# Motor_Control.net
KiCad netlist of a schematic drawn in Altium Designer
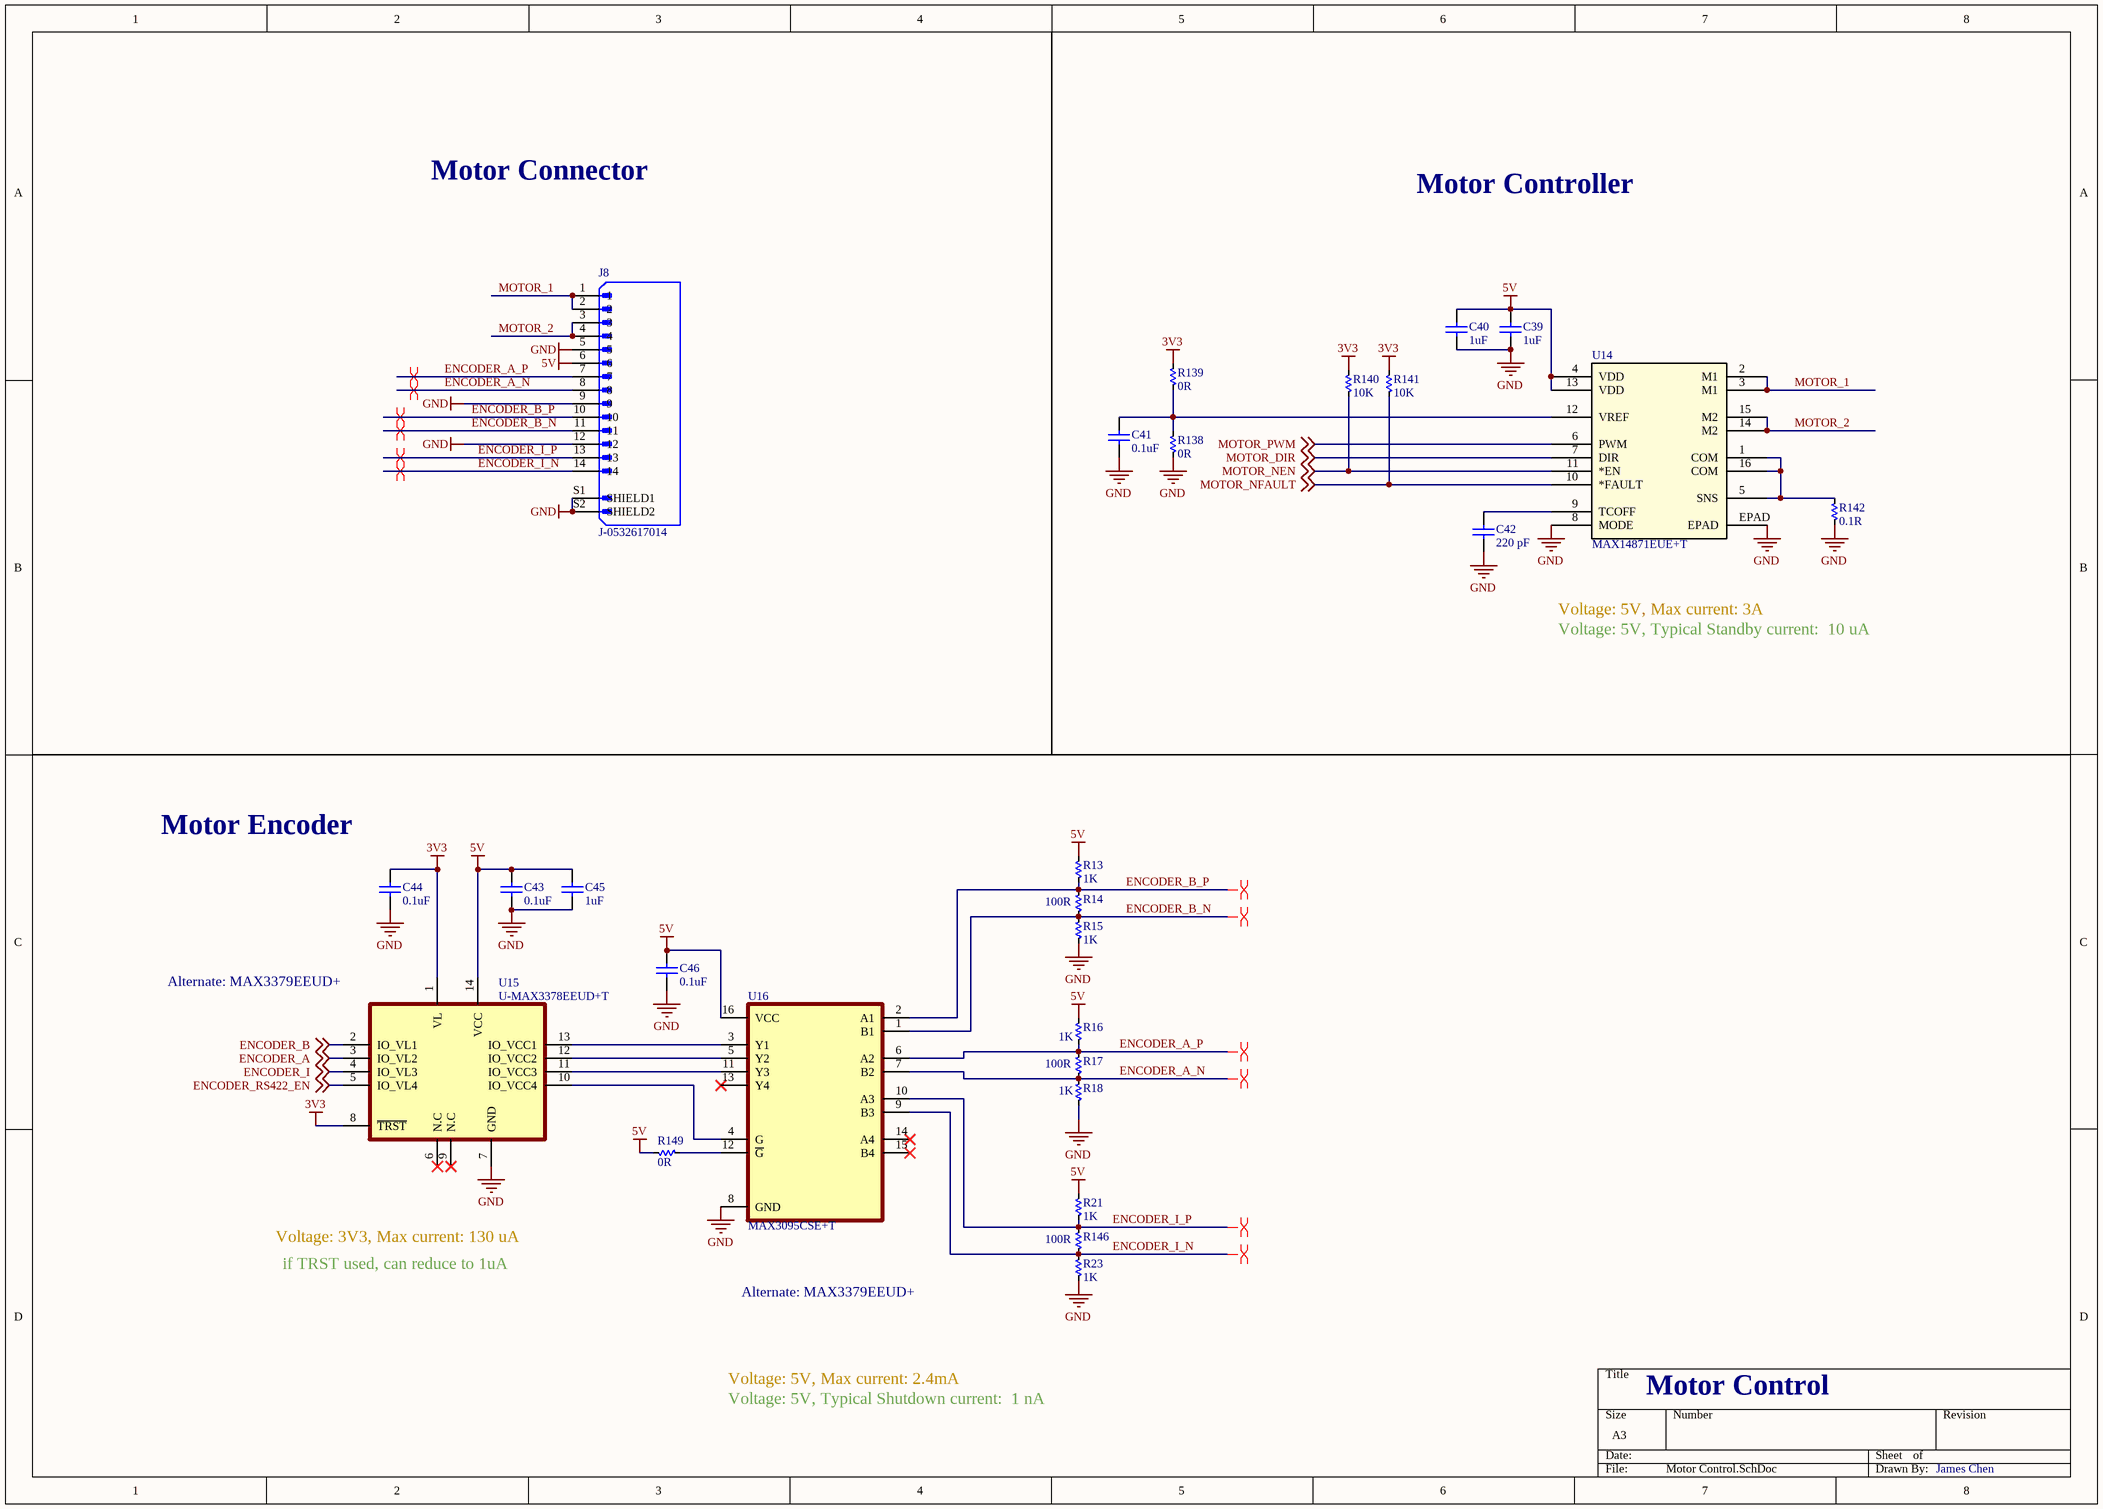
[diagram p0: Motor Control.SchDoc]

(export (version "E")
  (design (tool "Eeschema 10.0.6"))
  (components
    (comp (ref "C39")
      (value "1uF")
      (footprint "0603")
      (description "CAP CER 1UF 25V X7R 0603")
      (fields (field (name "DISTRIBUTOR PART #") "311-1802-1-ND") (field (name "MANUFACTURER") "Yageo"))
      (libsource (lib "OBC Development Board") (part "CC-105-K-25V-X7R-0603"))
    )
    (comp (ref "C40")
      (value "1uF")
      (footprint "0603")
      (description "CAP CER 1UF 25V X7R 0603")
      (fields (field (name "DISTRIBUTOR PART #") "311-1802-1-ND") (field (name "MANUFACTURER") "Yageo"))
      (libsource (lib "OBC Development Board") (part "CC-105-K-25V-X7R-0603"))
    )
    (comp (ref "C41")
      (value "0.1uF")
      (footprint "0603")
      (description "0.1 µF ±10% 25V Ceramic Capacitor X7R 0603 (1608 Metric)")
      (fields
        (field (name "DISTRIBUTOR PART #") "1276-1006-1-ND")
        (field (name "MANUFACTURER") "Samsung Electro-Mechanics")
      )
      (libsource (lib "OBC Development Board") (part "CC-104-K-25V-X7R-0603"))
    )
    (comp (ref "C42")
      (value "220 pF")
      (footprint "0603")
      (description "15 pF ±1% 50V Ceramic Capacitor C0G, NP0 0201 (0603 Metric)")
      (fields
        (field (name "DISTRIBUTOR PART #") "1276-1048-1-ND")
        (field (name "MANUFACTURER") "Samsung Electro-Mechanics")
      )
      (libsource (lib "OBC Development Board") (part "CC-228-J-50V-C0G-0603"))
    )
    (comp (ref "C43")
      (value "0.1uF")
      (footprint "0603")
      (description "0.1 µF ±10% 25V Ceramic Capacitor X7R 0603 (1608 Metric)")
      (fields
        (field (name "DISTRIBUTOR PART #") "1276-1006-1-ND")
        (field (name "MANUFACTURER") "Samsung Electro-Mechanics")
      )
      (libsource (lib "OBC Development Board") (part "CC-104-K-25V-X7R-0603"))
    )
    (comp (ref "C44")
      (value "0.1uF")
      (footprint "0603")
      (description "0.1 µF ±10% 25V Ceramic Capacitor X7R 0603 (1608 Metric)")
      (fields
        (field (name "DISTRIBUTOR PART #") "1276-1006-1-ND")
        (field (name "MANUFACTURER") "Samsung Electro-Mechanics")
      )
      (libsource (lib "OBC Development Board") (part "CC-104-K-25V-X7R-0603"))
    )
    (comp (ref "C45")
      (value "1uF")
      (footprint "0603")
      (description "CAP CER 1UF 25V X7R 0603")
      (fields (field (name "DISTRIBUTOR PART #") "311-1802-1-ND") (field (name "MANUFACTURER") "Yageo"))
      (libsource (lib "OBC Development Board") (part "CC-105-K-25V-X7R-0603"))
    )
    (comp (ref "C46")
      (value "0.1uF")
      (footprint "0603")
      (description "0.1 µF ±10% 25V Ceramic Capacitor X7R 0603 (1608 Metric)")
      (fields
        (field (name "DISTRIBUTOR PART #") "1276-1006-1-ND")
        (field (name "MANUFACTURER") "Samsung Electro-Mechanics")
      )
      (libsource (lib "OBC Development Board") (part "CC-104-K-25V-X7R-0603"))
    )
    (comp (ref "J8")
      (value "J-0532617014")
      (footprint "J-532617014")
      (description "Connector Header Surface Mount, Right Angle 14 position 0.049 (1.25mm)")
      (fields (field (name "MANUFACTURER") "Molex") (field (name "MANUFACTURER PART #") "0532617014"))
      (libsource (lib "OBC Development Board") (part "J-0532617014"))
    )
    (comp (ref "R13")
      (value "1K")
      (footprint "0603")
      (description "RES SMD 1K OHM 1% 1/16W 0603")
      (fields
        (field (name "DISTRIBUTOR PART #") "A102226CT-ND")
        (field (name "MANUFACTURER") "TE Connectivity Passive Product")
      )
      (libsource (lib "OBC Development Board") (part "RT-1K0-F-1/16W-0603"))
    )
    (comp (ref "R14")
      (value "100R")
      (footprint "0603")
      (description "RES SMD 100 OHM 0.5% 1/16W 0603")
      (fields (field (name "DISTRIBUTOR PART #") "RR08P100DCT-ND") (field (name "MANUFACTURER") "Susumu"))
      (libsource (lib "OBC Development Board") (part "RT-100R-F-1/16W-0603"))
    )
    (comp (ref "R15")
      (value "1K")
      (footprint "0603")
      (description "RES SMD 1K OHM 1% 1/16W 0603")
      (fields
        (field (name "DISTRIBUTOR PART #") "A102226CT-ND")
        (field (name "MANUFACTURER") "TE Connectivity Passive Product")
      )
      (libsource (lib "OBC Development Board") (part "RT-1K0-F-1/16W-0603"))
    )
    (comp (ref "R16")
      (value "1K")
      (footprint "0603")
      (description "RES SMD 1K OHM 1% 1/16W 0603")
      (fields
        (field (name "DISTRIBUTOR PART #") "A102226CT-ND")
        (field (name "MANUFACTURER") "TE Connectivity Passive Product")
      )
      (libsource (lib "OBC Development Board") (part "RT-1K0-F-1/16W-0603"))
    )
    (comp (ref "R17")
      (value "100R")
      (footprint "0603")
      (description "RES SMD 100 OHM 0.5% 1/16W 0603")
      (fields (field (name "DISTRIBUTOR PART #") "RR08P100DCT-ND") (field (name "MANUFACTURER") "Susumu"))
      (libsource (lib "OBC Development Board") (part "RT-100R-F-1/16W-0603"))
    )
    (comp (ref "R18")
      (value "1K")
      (footprint "0603")
      (description "RES SMD 1K OHM 1% 1/16W 0603")
      (fields
        (field (name "DISTRIBUTOR PART #") "A102226CT-ND")
        (field (name "MANUFACTURER") "TE Connectivity Passive Product")
      )
      (libsource (lib "OBC Development Board") (part "RT-1K0-F-1/16W-0603"))
    )
    (comp (ref "R21")
      (value "1K")
      (footprint "0603")
      (description "RES SMD 1K OHM 1% 1/16W 0603")
      (fields
        (field (name "DISTRIBUTOR PART #") "A102226CT-ND")
        (field (name "MANUFACTURER") "TE Connectivity Passive Product")
      )
      (libsource (lib "OBC Development Board") (part "RT-1K0-F-1/16W-0603"))
    )
    (comp (ref "R23")
      (value "1K")
      (footprint "0603")
      (description "RES SMD 1K OHM 1% 1/16W 0603")
      (fields
        (field (name "DISTRIBUTOR PART #") "A102226CT-ND")
        (field (name "MANUFACTURER") "TE Connectivity Passive Product")
      )
      (libsource (lib "OBC Development Board") (part "RT-1K0-F-1/16W-0603"))
    )
    (comp (ref "R138")
      (value "0R")
      (footprint "0603")
      (description "0 Ohms Jumper 0.1W, 1/10W Chip Resistor 0603 (1608 Metric) Automotive AEC-Q200 Thick Film")
      (fields
        (field (name "DISTRIBUTOR PART #") "RMCF0603ZT0R00CT-ND")
        (field (name "MANUFACTURER") "Stackpole Electronics Inc")
      )
      (libsource (lib "OBC Development Board") (part "RT-0R00-F-1/10W-0603"))
    )
    (comp (ref "R139")
      (value "0R")
      (footprint "0603")
      (description "0 Ohms Jumper 0.1W, 1/10W Chip Resistor 0603 (1608 Metric) Automotive AEC-Q200 Thick Film")
      (fields
        (field (name "DISTRIBUTOR PART #") "RMCF0603ZT0R00CT-ND")
        (field (name "MANUFACTURER") "Stackpole Electronics Inc")
      )
      (libsource (lib "OBC Development Board") (part "RT-0R00-F-1/10W-0603"))
    )
    (comp (ref "R140")
      (value "10K")
      (footprint "0603")
      (description "10 kOhms ±0.1% 0.063W, 1/16W Chip Resistor 0603 (1608 Metric) - Thin Film")
      (fields
        (field (name "DISTRIBUTOR PART #") "A119886CT-ND")
        (field (name "MANUFACTURER") "TE Connectivity Passive Product")
      )
      (libsource (lib "OBC Development Board") (part "RT-10K0-F-1/16W-0603"))
    )
    (comp (ref "R141")
      (value "10K")
      (footprint "0603")
      (description "10 kOhms ±0.1% 0.063W, 1/16W Chip Resistor 0603 (1608 Metric) - Thin Film")
      (fields
        (field (name "DISTRIBUTOR PART #") "A119886CT-ND")
        (field (name "MANUFACTURER") "TE Connectivity Passive Product")
      )
      (libsource (lib "OBC Development Board") (part "RT-10K0-F-1/16W-0603"))
    )
    (comp (ref "R142")
      (value "0.1R")
      (footprint "2512")
      (description "RES 0.1 OHM 1% 3W 2512")
      (fields
        (field (name "DISTRIBUTOR PART #") "CRA2512-FZ-R100ELFCT-ND")
        (field (name "MANUFACTURER") "Bourns Inc.")
      )
      (libsource (lib "OBC Development Board") (part "RT-0R1-3W-2512"))
    )
    (comp (ref "R146")
      (value "100R")
      (footprint "0603")
      (description "RES SMD 100 OHM 0.5% 1/16W 0603")
      (fields (field (name "DISTRIBUTOR PART #") "RR08P100DCT-ND") (field (name "MANUFACTURER") "Susumu"))
      (libsource (lib "OBC Development Board") (part "RT-100R-F-1/16W-0603"))
    )
    (comp (ref "R149")
      (value "0R")
      (footprint "0603")
      (description "0 Ohms Jumper 0.1W, 1/10W Chip Resistor 0603 (1608 Metric) Automotive AEC-Q200 Thick Film")
      (fields
        (field (name "DISTRIBUTOR PART #") "RMCF0603ZT0R00CT-ND")
        (field (name "MANUFACTURER") "Stackpole Electronics Inc")
      )
      (libsource (lib "OBC Development Board") (part "RT-0R00-F-1/10W-0603"))
    )
    (comp (ref "U14")
      (value "MAX14871EUE+T")
      (footprint "U-MAX14871EUE+T")
      (description "IC MOTOR DRIVER 4.5V-36V 16TSSOP")
      (fields
        (field (name "MANUFACTURER") "Maxim Integrated Products")
        (field (name "DISTRIBUTOR PART #") "MAX14871EUE+CT-ND")
      )
      (libsource (lib "OBC Development Board") (part "U-MAX14871EUE+T"))
    )
    (comp (ref "U15")
      (value "U-MAX3378EEUD+T")
      (footprint "OBC Development Board:U-MAX3378EEUD+T")
      (description "IC TRNSLTR BIDIRECTIONAL 14TSSOP")
      (fields
        (field (name "MANUFACTURER PART #") "MAX3378EEUD+T")
        (field (name "MANUFACTURER") "Maxim Integrated")
      )
      (libsource (lib "OBC Development Board") (part "U-MAX3378EEUD+T"))
    )
    (comp (ref "U16")
      (value "MAX3095CSE+T")
      (footprint "U-MAX3095CSE+T")
      (description "IC RECEIVER 0/4 16SO")
      (fields
        (field (name "DISTRIBUTOR PART #") "MAX3095CSE+TCT-ND")
        (field (name "MANUFACTURER") "Maxim Integrated")
      )
      (libsource (lib "OBC Development Board") (part "U-MAX3095CSE+T"))
    )
  )
  (nets
    (net (code "2") (name "/ENCODER_A_N") (class "Default")
      (node (ref "J8") (pin "8") (pinfunction "8_8") (pintype "passive"))
      (node (ref "R17") (pin "1") (pintype "passive"))
      (node (ref "R18") (pin "2") (pintype "passive"))
      (node (ref "U16") (pin "7") (pinfunction "B2_7") (pintype "passive"))
    )
    (net (code "3") (name "/ENCODER_A_P") (class "Default")
      (node (ref "J8") (pin "7") (pinfunction "7_7") (pintype "passive"))
      (node (ref "R16") (pin "1") (pintype "passive"))
      (node (ref "R17") (pin "2") (pintype "passive"))
      (node (ref "U16") (pin "6") (pinfunction "A2_6") (pintype "passive"))
    )
    (net (code "4") (name "/ENCODER_B_N") (class "Default")
      (node (ref "J8") (pin "11") (pinfunction "11_11") (pintype "passive"))
      (node (ref "R14") (pin "1") (pintype "passive"))
      (node (ref "R15") (pin "2") (pintype "passive"))
      (node (ref "U16") (pin "1") (pinfunction "B1_1") (pintype "passive"))
    )
    (net (code "5") (name "/ENCODER_B_P") (class "Default")
      (node (ref "J8") (pin "10") (pinfunction "10_10") (pintype "passive"))
      (node (ref "R13") (pin "1") (pintype "passive"))
      (node (ref "R14") (pin "2") (pintype "passive"))
      (node (ref "U16") (pin "2") (pinfunction "A1_2") (pintype "passive"))
    )
    (net (code "6") (name "/ENCODER_I_N") (class "Default")
      (node (ref "J8") (pin "14") (pinfunction "14_14") (pintype "passive"))
      (node (ref "R146") (pin "1") (pintype "passive"))
      (node (ref "R23") (pin "2") (pintype "passive"))
      (node (ref "U16") (pin "9") (pinfunction "B3_9") (pintype "passive"))
    )
    (net (code "7") (name "/ENCODER_I_P") (class "Default")
      (node (ref "J8") (pin "13") (pinfunction "13_13") (pintype "passive"))
      (node (ref "R146") (pin "2") (pintype "passive"))
      (node (ref "R21") (pin "1") (pintype "passive"))
      (node (ref "U16") (pin "10") (pinfunction "A3_10") (pintype "passive"))
    )
    (net (code "8") (name "/MOTOR_1") (class "Default")
      (node (ref "J8") (pin "1") (pinfunction "1_1") (pintype "passive"))
      (node (ref "J8") (pin "2") (pinfunction "2_2") (pintype "passive"))
      (node (ref "U14") (pin "2") (pinfunction "M1_2") (pintype "passive"))
      (node (ref "U14") (pin "3") (pinfunction "M1_3") (pintype "passive"))
    )
    (net (code "9") (name "/MOTOR_2") (class "Default")
      (node (ref "J8") (pin "3") (pinfunction "3_3") (pintype "passive"))
      (node (ref "J8") (pin "4") (pinfunction "4_4") (pintype "passive"))
      (node (ref "U14") (pin "14") (pinfunction "M2_14") (pintype "passive"))
      (node (ref "U14") (pin "15") (pinfunction "M2_15") (pintype "passive"))
    )
    (net (code "10") (name "3V3") (class "Default")
      (node (ref "C44") (pin "1") (pinfunction "1_1") (pintype "passive"))
      (node (ref "R139") (pin "2") (pintype "passive"))
      (node (ref "R140") (pin "1") (pintype "passive"))
      (node (ref "R141") (pin "1") (pintype "passive"))
      (node (ref "U15") (pin "1") (pinfunction "VL_1") (pintype "power_in"))
      (node (ref "U15") (pin "8") (pinfunction "~{TRST}_8") (pintype "passive"))
    )
    (net (code "11") (name "5V") (class "Default")
      (node (ref "C39") (pin "1") (pinfunction "1_1") (pintype "passive"))
      (node (ref "C40") (pin "1") (pinfunction "1_1") (pintype "passive"))
      (node (ref "C43") (pin "1") (pinfunction "1_1") (pintype "passive"))
      (node (ref "C45") (pin "2") (pinfunction "2_2") (pintype "passive"))
      (node (ref "C46") (pin "1") (pinfunction "1_1") (pintype "passive"))
      (node (ref "J8") (pin "6") (pinfunction "6_6") (pintype "passive"))
      (node (ref "R13") (pin "2") (pintype "passive"))
      (node (ref "R149") (pin "2") (pintype "passive"))
      (node (ref "R16") (pin "2") (pintype "passive"))
      (node (ref "R21") (pin "2") (pintype "passive"))
      (node (ref "U14") (pin "13") (pinfunction "VDD_13") (pintype "passive"))
      (node (ref "U14") (pin "4") (pinfunction "VDD_4") (pintype "passive"))
      (node (ref "U15") (pin "14") (pinfunction "VCC_14") (pintype "power_in"))
      (node (ref "U16") (pin "16") (pinfunction "VCC_16") (pintype "passive"))
    )
    (net (code "12") (name "ENCODER_A") (class "Default")
      (node (ref "U15") (pin "3") (pinfunction "IO_VL2_3") (pintype "passive"))
    )
    (net (code "13") (name "ENCODER_B") (class "Default")
      (node (ref "U15") (pin "2") (pinfunction "IO_VL1_2") (pintype "passive"))
    )
    (net (code "14") (name "ENCODER_I") (class "Default")
      (node (ref "U15") (pin "4") (pinfunction "IO_VL3_4") (pintype "passive"))
    )
    (net (code "15") (name "ENCODER_RS422_EN") (class "Default")
      (node (ref "U15") (pin "5") (pinfunction "IO_VL4_5") (pintype "passive"))
    )
    (net (code "16") (name "GND") (class "Default")
      (node (ref "C39") (pin "2") (pinfunction "2_2") (pintype "passive"))
      (node (ref "C40") (pin "2") (pinfunction "2_2") (pintype "passive"))
      (node (ref "C41") (pin "2") (pinfunction "2_2") (pintype "passive"))
      (node (ref "C42") (pin "1") (pinfunction "1_1") (pintype "passive"))
      (node (ref "C43") (pin "2") (pinfunction "2_2") (pintype "passive"))
      (node (ref "C44") (pin "2") (pinfunction "2_2") (pintype "passive"))
      (node (ref "C45") (pin "1") (pinfunction "1_1") (pintype "passive"))
      (node (ref "C46") (pin "2") (pinfunction "2_2") (pintype "passive"))
      (node (ref "J8") (pin "12") (pinfunction "12_12") (pintype "passive"))
      (node (ref "J8") (pin "5") (pinfunction "5_5") (pintype "passive"))
      (node (ref "J8") (pin "9") (pinfunction "9_9") (pintype "passive"))
      (node (ref "J8") (pin "S1") (pinfunction "SHIELD1_S1") (pintype "passive"))
      (node (ref "J8") (pin "S2") (pinfunction "SHIELD2_S2") (pintype "passive"))
      (node (ref "R138") (pin "2") (pintype "passive"))
      (node (ref "R142") (pin "1") (pintype "passive"))
      (node (ref "R15") (pin "1") (pintype "passive"))
      (node (ref "R18") (pin "1") (pintype "passive"))
      (node (ref "R23") (pin "1") (pintype "passive"))
      (node (ref "U14") (pin "8") (pinfunction "MODE_8") (pintype "passive"))
      (node (ref "U14") (pin "EPAD") (pinfunction "EPAD_EPAD") (pintype "passive"))
      (node (ref "U15") (pin "7") (pinfunction "GND_7") (pintype "passive"))
      (node (ref "U16") (pin "8") (pinfunction "GND_8") (pintype "passive"))
    )
    (net (code "17") (name "MOTOR_DIR") (class "Default")
      (node (ref "U14") (pin "7") (pinfunction "DIR_7") (pintype "passive"))
    )
    (net (code "18") (name "MOTOR_NEN") (class "Default")
      (node (ref "R140") (pin "2") (pintype "passive"))
      (node (ref "U14") (pin "11") (pinfunction "*EN_11") (pintype "passive"))
    )
    (net (code "19") (name "MOTOR_NFAULT") (class "Default")
      (node (ref "R141") (pin "2") (pintype "passive"))
      (node (ref "U14") (pin "10") (pinfunction "*FAULT_10") (pintype "passive"))
    )
    (net (code "20") (name "MOTOR_PWM") (class "Default")
      (node (ref "U14") (pin "6") (pinfunction "PWM_6") (pintype "passive"))
    )
    (net (code "21") (name "Net-(U14-SNS)") (class "Default")
      (node (ref "R142") (pin "2") (pintype "passive"))
      (node (ref "U14") (pin "1") (pinfunction "COM_1") (pintype "passive"))
      (node (ref "U14") (pin "16") (pinfunction "COM_16") (pintype "passive"))
      (node (ref "U14") (pin "5") (pinfunction "SNS_5") (pintype "passive"))
    )
    (net (code "22") (name "Net-(U14-TCOFF)") (class "Default")
      (node (ref "C42") (pin "2") (pinfunction "2_2") (pintype "passive"))
      (node (ref "U14") (pin "9") (pinfunction "TCOFF_9") (pintype "passive"))
    )
    (net (code "23") (name "Net-(U14-VREF)") (class "Default")
      (node (ref "C41") (pin "1") (pinfunction "1_1") (pintype "passive"))
      (node (ref "R138") (pin "1") (pintype "passive"))
      (node (ref "R139") (pin "1") (pintype "passive"))
      (node (ref "U14") (pin "12") (pinfunction "VREF_12") (pintype "passive"))
    )
    (net (code "24") (name "Net-(U15-IO_VCC1)") (class "Default")
      (node (ref "U15") (pin "13") (pinfunction "IO_VCC1_13") (pintype "passive"))
      (node (ref "U16") (pin "3") (pinfunction "Y1_3") (pintype "passive"))
    )
    (net (code "25") (name "Net-(U15-IO_VCC2)") (class "Default")
      (node (ref "U15") (pin "12") (pinfunction "IO_VCC2_12") (pintype "passive"))
      (node (ref "U16") (pin "5") (pinfunction "Y2_5") (pintype "passive"))
    )
    (net (code "26") (name "Net-(U15-IO_VCC3)") (class "Default")
      (node (ref "U15") (pin "11") (pinfunction "IO_VCC3_11") (pintype "passive"))
      (node (ref "U16") (pin "11") (pinfunction "Y3_11") (pintype "passive"))
    )
    (net (code "27") (name "Net-(U15-IO_VCC4)") (class "Default")
      (node (ref "U15") (pin "10") (pinfunction "IO_VCC4_10") (pintype "passive"))
      (node (ref "U16") (pin "4") (pinfunction "G_4") (pintype "passive"))
    )
    (net (code "28") (name "Net-(U16-~{G})") (class "Default")
      (node (ref "R149") (pin "1") (pintype "passive"))
      (node (ref "U16") (pin "12") (pinfunction "~{G}_12") (pintype "passive"))
    )
    (net (code "29") (name "unconnected-(U15-N.C-Pad6)") (class "Default")
      (node (ref "U15") (pin "6") (pinfunction "N.C_6") (pintype "passive+no_connect"))
    )
    (net (code "30") (name "unconnected-(U15-N.C-Pad9)") (class "Default")
      (node (ref "U15") (pin "9") (pinfunction "N.C_9") (pintype "passive+no_connect"))
    )
    (net (code "31") (name "unconnected-(U16-A4-Pad14)") (class "Default")
      (node (ref "U16") (pin "14") (pinfunction "A4_14") (pintype "passive+no_connect"))
    )
    (net (code "32") (name "unconnected-(U16-B4-Pad15)") (class "Default")
      (node (ref "U16") (pin "15") (pinfunction "B4_15") (pintype "passive+no_connect"))
    )
    (net (code "33") (name "unconnected-(U16-Y4-Pad13)") (class "Default")
      (node (ref "U16") (pin "13") (pinfunction "Y4_13") (pintype "passive+no_connect"))
    )
  )
)
